# Multimeter1_2.net
KiCad netlist of a schematic drawn in EAGLE
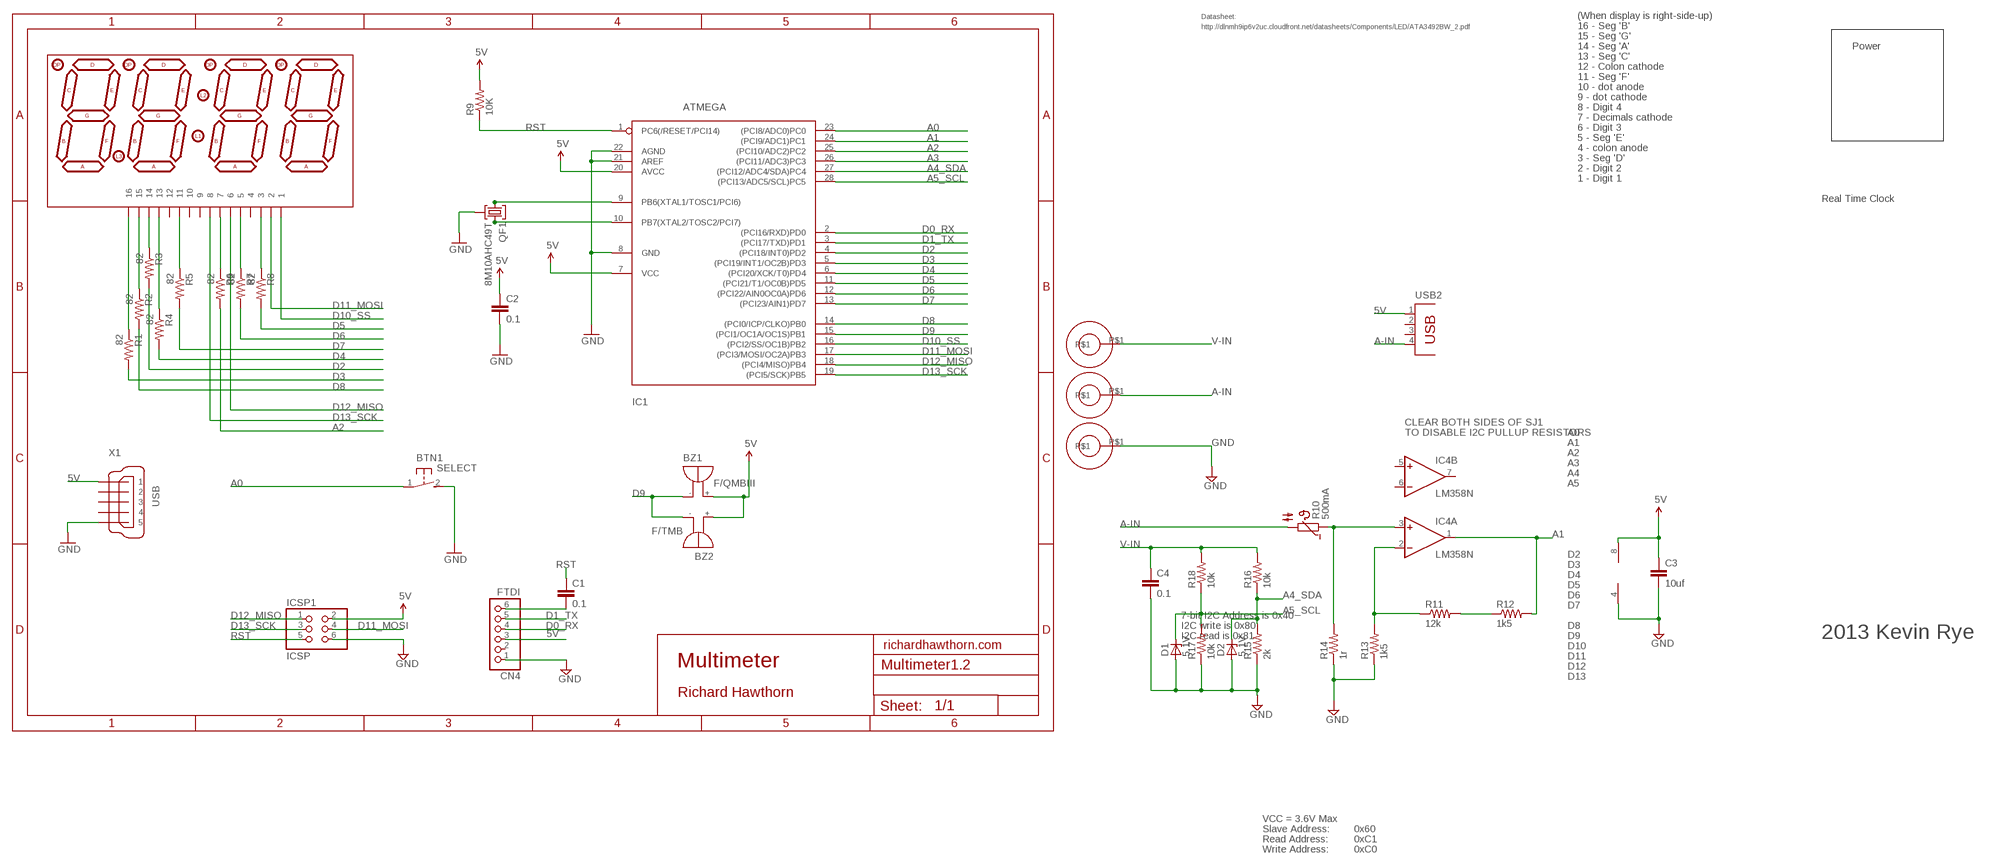
[diagram p0: schematic, sheet 1]

(export (version "E")
  (design (tool "Eeschema 10.0.6"))
  (components
    (comp (ref "BTN1")
      (value "SELECT")
      (footprint "eagle-import:DTS-3")
      (libsource (lib "eagle-import") (part "DTS-3"))
    )
    (comp (ref "BZ1")
      (value "F/QMBIII")
      (footprint "eagle-import:F_QMBIII")
      (libsource (lib "eagle-import") (part "F/QMBIII"))
    )
    (comp (ref "BZ2")
      (value "F/TMB")
      (footprint "eagle-import:F_TMB")
      (libsource (lib "eagle-import") (part "F/TMB"))
    )
    (comp (ref "C1")
      (value "0.1")
      (footprint "eagle-import:CAP-PTH-SMALL2")
      (libsource (lib "eagle-import") (part "CAPPTH2"))
    )
    (comp (ref "C2")
      (value "0.1")
      (footprint "eagle-import:CAP-PTH-SMALL2")
      (libsource (lib "eagle-import") (part "CAPPTH2"))
    )
    (comp (ref "C3")
      (value "10uf")
      (footprint "eagle-import:CAP-PTH-SMALL2")
      (libsource (lib "eagle-import") (part "CAPPTH2"))
    )
    (comp (ref "C4")
      (value "0.1")
      (footprint "eagle-import:CAP-PTH-SMALL2")
      (libsource (lib "eagle-import") (part "CAPPTH2"))
    )
    (comp (ref "CN4")
      (value "FTDI")
      (footprint "eagle-import:1X06")
      (libsource (lib "eagle-import") (part "PINHD-1X6"))
    )
    (comp (ref "D1")
      (value "5.1V")
      (footprint "eagle-import:DO34Z7")
      (libsource (lib "eagle-import") (part "BZX90"))
    )
    (comp (ref "D2")
      (value "5.1V")
      (footprint "eagle-import:DO34Z7")
      (libsource (lib "eagle-import") (part "BZX90"))
    )
    (comp (ref "IC1")
      (value "ATMEGA")
      (footprint "eagle-import:DIL28-3-ROUND")
      (libsource (lib "eagle-import") (part "ATMEGA168PROUND"))
    )
    (comp (ref "IC4")
      (value "LM358N")
      (footprint "eagle-import:DIL08")
      (libsource (lib "eagle-import") (part "LM358N"))
    )
    (comp (ref "ICSP1")
      (value "ICSP")
      (footprint "eagle-import:2X03")
      (libsource (lib "eagle-import") (part "PINHD-2X3"))
    )
    (comp (ref "LED1")
      (value "7SEG-4DIGIT")
      (footprint "eagle-import:SPARKFUN_7-SEGMENT-4DIGIT")
      (libsource (lib "eagle-import") (part "7SEG-4DIGIT"))
    )
    (comp (ref "QF1")
      (value "8M10AHC49T")
      (footprint "eagle-import:HC49U")
      (libsource (lib "eagle-import") (part "8M10AHC49T"))
    )
    (comp (ref "R1")
      (value "82")
      (footprint "eagle-import:0204_7")
      (libsource (lib "eagle-import") (part "R-US_0204/7"))
    )
    (comp (ref "R2")
      (value "82")
      (footprint "eagle-import:0204_7")
      (libsource (lib "eagle-import") (part "R-US_0204/7"))
    )
    (comp (ref "R3")
      (value "82")
      (footprint "eagle-import:0204_7")
      (libsource (lib "eagle-import") (part "R-US_0204/7"))
    )
    (comp (ref "R4")
      (value "82")
      (footprint "eagle-import:0204_7")
      (libsource (lib "eagle-import") (part "R-US_0204/7"))
    )
    (comp (ref "R5")
      (value "82")
      (footprint "eagle-import:0204_7")
      (libsource (lib "eagle-import") (part "R-US_0204/7"))
    )
    (comp (ref "R6")
      (value "82")
      (footprint "eagle-import:0204_7")
      (libsource (lib "eagle-import") (part "R-US_0204/7"))
    )
    (comp (ref "R7")
      (value "82")
      (footprint "eagle-import:0204_7")
      (libsource (lib "eagle-import") (part "R-US_0204/7"))
    )
    (comp (ref "R8")
      (value "82")
      (footprint "eagle-import:0204_7")
      (libsource (lib "eagle-import") (part "R-US_0204/7"))
    )
    (comp (ref "R9")
      (value "10K")
      (footprint "eagle-import:0204_7")
      (libsource (lib "eagle-import") (part "R-US_0204/7"))
    )
    (comp (ref "R10")
      (value "500mA")
      (footprint "eagle-import:B57164")
      (fields (field (name "MPN") "B57164K474K52"))
      (libsource (lib "eagle-import") (part "B57164"))
    )
    (comp (ref "R11")
      (value "12k")
      (footprint "eagle-import:0204_7")
      (libsource (lib "eagle-import") (part "R-US_0204/7"))
    )
    (comp (ref "R12")
      (value "1k5")
      (footprint "eagle-import:0204_7")
      (libsource (lib "eagle-import") (part "R-US_0204/7"))
    )
    (comp (ref "R13")
      (value "1k5")
      (footprint "eagle-import:0204_7")
      (libsource (lib "eagle-import") (part "R-US_0204/7"))
    )
    (comp (ref "R14")
      (value "1r")
      (footprint "eagle-import:0204_7")
      (libsource (lib "eagle-import") (part "R-US_0204/7"))
    )
    (comp (ref "R15")
      (value "2k")
      (footprint "eagle-import:0204_7")
      (libsource (lib "eagle-import") (part "R-US_0204/7"))
    )
    (comp (ref "R16")
      (value "10k")
      (footprint "eagle-import:0204_7")
      (libsource (lib "eagle-import") (part "R-US_0204/7"))
    )
    (comp (ref "R17")
      (value "10k")
      (footprint "eagle-import:0204_7")
      (libsource (lib "eagle-import") (part "R-US_0204/7"))
    )
    (comp (ref "R18")
      (value "10k")
      (footprint "eagle-import:0204_7")
      (libsource (lib "eagle-import") (part "R-US_0204/7"))
    )
    (comp (ref "U$1")
      (value "BANANA")
      (footprint "eagle-import:BANANA")
      (libsource (lib "eagle-import") (part "BANANA"))
    )
    (comp (ref "U$5")
      (value "BANANA")
      (footprint "eagle-import:BANANA")
      (libsource (lib "eagle-import") (part "BANANA"))
    )
    (comp (ref "U$6")
      (value "BANANA")
      (footprint "eagle-import:BANANA")
      (libsource (lib "eagle-import") (part "BANANA"))
    )
    (comp (ref "USB2")
      (value "PN87520")
      (footprint "eagle-import:PN87520")
      (libsource (lib "eagle-import") (part "PN87520"))
    )
    (comp (ref "X1")
      (value "USB")
      (footprint "eagle-import:32005-601")
      (libsource (lib "eagle-import") (part "MINI-USB_SHIELD5P2-32005-601"))
    )
  )
  (nets
    (net (code "1") (name "/A-IN") (class "Default")
      (node (ref "R10") (pin "2") (pinfunction "2_2") (pintype "passive"))
      (node (ref "U$5") (pin "P$1") (pinfunction "P$1_P$1") (pintype "bidirectional"))
      (node (ref "USB2") (pin "4") (pinfunction "4_4") (pintype "passive"))
    )
    (net (code "2") (name "/A0") (class "Default")
      (node (ref "BTN1") (pin "1") (pinfunction "1_1") (pintype "passive"))
      (node (ref "IC1") (pin "23") (pinfunction "(PCI8/ADC0)PC0_23") (pintype "bidirectional"))
    )
    (net (code "3") (name "/A1") (class "Default")
      (node (ref "IC1") (pin "24") (pinfunction "(PCI9/ADC1)PC1_24") (pintype "bidirectional"))
      (node (ref "IC4") (pin "1") (pinfunction "OUT_1") (pintype "output"))
      (node (ref "R12") (pin "2") (pinfunction "2_2") (pintype "passive"))
    )
    (net (code "4") (name "/A2") (class "Default")
      (node (ref "IC1") (pin "25") (pinfunction "(PCI10/ADC2)PC2_25") (pintype "bidirectional"))
      (node (ref "R6") (pin "2") (pinfunction "2_2") (pintype "passive"))
    )
    (net (code "5") (name "/A3") (class "Default")
      (node (ref "IC1") (pin "26") (pinfunction "(PCI11/ADC3)PC3_26") (pintype "bidirectional"))
    )
    (net (code "6") (name "/A4_SDA") (class "Default")
      (node (ref "D2") (pin "C") (pinfunction "C_C") (pintype "passive"))
      (node (ref "IC1") (pin "27") (pinfunction "(PCI12/ADC4/SDA)PC4_27") (pintype "bidirectional"))
      (node (ref "R15") (pin "2") (pinfunction "2_2") (pintype "passive"))
      (node (ref "R16") (pin "1") (pinfunction "1_1") (pintype "passive"))
    )
    (net (code "7") (name "/A5_SCL") (class "Default")
      (node (ref "D1") (pin "C") (pinfunction "C_C") (pintype "passive"))
      (node (ref "IC1") (pin "28") (pinfunction "(PCI13/ADC5/SCL)PC5_28") (pintype "bidirectional"))
      (node (ref "R17") (pin "2") (pinfunction "2_2") (pintype "passive"))
      (node (ref "R18") (pin "1") (pinfunction "1_1") (pintype "passive"))
    )
    (net (code "8") (name "/D0_RX") (class "Default")
      (node (ref "CN4") (pin "4") (pinfunction "4_4") (pintype "passive"))
      (node (ref "IC1") (pin "2") (pinfunction "(PCI16/RXD)PD0_2") (pintype "bidirectional"))
    )
    (net (code "9") (name "/D1_TX") (class "Default")
      (node (ref "CN4") (pin "5") (pinfunction "5_5") (pintype "passive"))
      (node (ref "IC1") (pin "3") (pinfunction "(PCI17/TXD)PD1_3") (pintype "bidirectional"))
    )
    (net (code "10") (name "/D2") (class "Default")
      (node (ref "IC1") (pin "4") (pinfunction "(PCI18/INT0)PD2_4") (pintype "bidirectional"))
      (node (ref "R3") (pin "2") (pinfunction "2_2") (pintype "passive"))
    )
    (net (code "11") (name "/D3") (class "Default")
      (node (ref "IC1") (pin "5") (pinfunction "(PCI19/INT1/OC2B)PD3_5") (pintype "bidirectional"))
      (node (ref "R1") (pin "2") (pinfunction "2_2") (pintype "passive"))
    )
    (net (code "12") (name "/D4") (class "Default")
      (node (ref "IC1") (pin "6") (pinfunction "(PCI20/XCK/T0)PD4_6") (pintype "bidirectional"))
      (node (ref "R4") (pin "2") (pinfunction "2_2") (pintype "passive"))
    )
    (net (code "13") (name "/D5") (class "Default")
      (node (ref "IC1") (pin "11") (pinfunction "(PCI21/T1/OC0B)PD5_11") (pintype "bidirectional"))
      (node (ref "R8") (pin "2") (pinfunction "2_2") (pintype "passive"))
    )
    (net (code "14") (name "/D6") (class "Default")
      (node (ref "IC1") (pin "12") (pinfunction "(PCI22/AIN0OC0A)PD6_12") (pintype "bidirectional"))
      (node (ref "R7") (pin "2") (pinfunction "2_2") (pintype "passive"))
    )
    (net (code "15") (name "/D7") (class "Default")
      (node (ref "IC1") (pin "13") (pinfunction "(PCI23/AIN1)PD7_13") (pintype "bidirectional"))
      (node (ref "R5") (pin "2") (pinfunction "2_2") (pintype "passive"))
    )
    (net (code "16") (name "/D8") (class "Default")
      (node (ref "IC1") (pin "14") (pinfunction "(PCI0/ICP/CLKO)PB0_14") (pintype "bidirectional"))
      (node (ref "R2") (pin "2") (pinfunction "2_2") (pintype "passive"))
    )
    (net (code "17") (name "/D9") (class "Default")
      (node (ref "BZ1") (pin "-") (pinfunction "+_-") (pintype "passive"))
      (node (ref "BZ2") (pin "-") (pinfunction "-_-") (pintype "passive"))
      (node (ref "IC1") (pin "15") (pinfunction "(PCI1/OC1A/OC1S)PB1_15") (pintype "bidirectional"))
    )
    (net (code "18") (name "/D10_SS") (class "Default")
      (node (ref "IC1") (pin "16") (pinfunction "(PCI2/SS/OC1B)PB2_16") (pintype "bidirectional"))
      (node (ref "LED1") (pin "1") (pinfunction "1_1") (pintype "bidirectional"))
    )
    (net (code "19") (name "/D11_MOSI") (class "Default")
      (node (ref "IC1") (pin "17") (pinfunction "(PCI3/MOSI/OC2A)PB3_17") (pintype "bidirectional"))
      (node (ref "ICSP1") (pin "4") (pinfunction "4_4") (pintype "passive"))
      (node (ref "LED1") (pin "2") (pinfunction "2_2") (pintype "bidirectional"))
    )
    (net (code "20") (name "/D12_MISO") (class "Default")
      (node (ref "IC1") (pin "18") (pinfunction "(PCI4/MISO)PB4_18") (pintype "bidirectional"))
      (node (ref "ICSP1") (pin "1") (pinfunction "1_1") (pintype "passive"))
      (node (ref "LED1") (pin "6") (pinfunction "6_6") (pintype "bidirectional"))
    )
    (net (code "21") (name "/D13_SCK") (class "Default")
      (node (ref "IC1") (pin "19") (pinfunction "(PCI5/SCK)PB5_19") (pintype "bidirectional"))
      (node (ref "ICSP1") (pin "3") (pinfunction "3_3") (pintype "passive"))
      (node (ref "LED1") (pin "8") (pinfunction "8_8") (pintype "bidirectional"))
    )
    (net (code "22") (name "/RST") (class "Default")
      (node (ref "C1") (pin "1") (pinfunction "1_1") (pintype "passive"))
      (node (ref "IC1") (pin "1") (pinfunction "PC6(/RESET/PCI14)_1") (pintype "bidirectional"))
      (node (ref "ICSP1") (pin "5") (pinfunction "5_5") (pintype "passive"))
      (node (ref "R9") (pin "1") (pinfunction "1_1") (pintype "passive"))
    )
    (net (code "23") (name "/V-IN") (class "Default")
      (node (ref "C4") (pin "1") (pinfunction "1_1") (pintype "passive"))
      (node (ref "R16") (pin "2") (pinfunction "2_2") (pintype "passive"))
      (node (ref "R18") (pin "2") (pinfunction "2_2") (pintype "passive"))
      (node (ref "U$1") (pin "P$1") (pinfunction "P$1_P$1") (pintype "bidirectional"))
    )
    (net (code "24") (name "5V") (class "Default")
      (node (ref "BZ1") (pin "+") (pinfunction "-_+") (pintype "passive"))
      (node (ref "BZ2") (pin "+") (pinfunction "+_+") (pintype "passive"))
      (node (ref "C2") (pin "1") (pinfunction "1_1") (pintype "passive"))
      (node (ref "C3") (pin "1") (pinfunction "1_1") (pintype "passive"))
      (node (ref "CN4") (pin "3") (pinfunction "3_3") (pintype "passive"))
      (node (ref "IC1") (pin "20") (pinfunction "AVCC_20") (pintype "bidirectional"))
      (node (ref "IC1") (pin "7") (pinfunction "VCC_7") (pintype "bidirectional"))
      (node (ref "IC4") (pin "8") (pinfunction "V+_8") (pintype "power_in"))
      (node (ref "ICSP1") (pin "2") (pinfunction "2_2") (pintype "passive"))
      (node (ref "R9") (pin "2") (pinfunction "2_2") (pintype "passive"))
      (node (ref "USB2") (pin "1") (pinfunction "1_1") (pintype "passive"))
      (node (ref "X1") (pin "1") (pinfunction "1_1") (pintype "passive"))
    )
    (net (code "25") (name "GND") (class "Default")
      (node (ref "BTN1") (pin "2") (pinfunction "2_2") (pintype "passive"))
      (node (ref "C2") (pin "2") (pinfunction "2_2") (pintype "passive"))
      (node (ref "C3") (pin "2") (pinfunction "2_2") (pintype "passive"))
      (node (ref "C4") (pin "2") (pinfunction "2_2") (pintype "passive"))
      (node (ref "CN4") (pin "1") (pinfunction "1_1") (pintype "passive"))
      (node (ref "D1") (pin "A") (pinfunction "A_A") (pintype "passive"))
      (node (ref "D2") (pin "A") (pinfunction "A_A") (pintype "passive"))
      (node (ref "IC1") (pin "21") (pinfunction "AREF_21") (pintype "bidirectional"))
      (node (ref "IC1") (pin "22") (pinfunction "AGND_22") (pintype "bidirectional"))
      (node (ref "IC1") (pin "8") (pinfunction "GND_8") (pintype "bidirectional"))
      (node (ref "IC4") (pin "4") (pinfunction "V-_4") (pintype "power_in"))
      (node (ref "ICSP1") (pin "6") (pinfunction "6_6") (pintype "passive"))
      (node (ref "QF1") (pin "2") (pinfunction "2_2") (pintype "passive"))
      (node (ref "R13") (pin "1") (pinfunction "1_1") (pintype "passive"))
      (node (ref "R14") (pin "1") (pinfunction "1_1") (pintype "passive"))
      (node (ref "R15") (pin "1") (pinfunction "1_1") (pintype "passive"))
      (node (ref "R17") (pin "1") (pinfunction "1_1") (pintype "passive"))
      (node (ref "U$6") (pin "P$1") (pinfunction "P$1_P$1") (pintype "bidirectional"))
      (node (ref "X1") (pin "5") (pinfunction "5_5") (pintype "passive"))
    )
    (net (code "26") (name "Net-(C1-Pad2)") (class "Default")
      (node (ref "C1") (pin "2") (pinfunction "2_2") (pintype "passive"))
      (node (ref "CN4") (pin "6") (pinfunction "6_6") (pintype "passive"))
    )
    (net (code "27") (name "Net-(IC1-PB6(XTAL1{slash}TOSC1{slash}PCI6))") (class "Default")
      (node (ref "IC1") (pin "9") (pinfunction "PB6(XTAL1/TOSC1/PCI6)_9") (pintype "bidirectional"))
      (node (ref "QF1") (pin "1") (pinfunction "1_1") (pintype "passive"))
    )
    (net (code "28") (name "Net-(IC1-PB7(XTAL2{slash}TOSC2{slash}PCI7))") (class "Default")
      (node (ref "IC1") (pin "10") (pinfunction "PB7(XTAL2/TOSC2/PCI7)_10") (pintype "bidirectional"))
      (node (ref "QF1") (pin "3") (pinfunction "3_3") (pintype "passive"))
    )
    (net (code "29") (name "Net-(IC4A-+IN)") (class "Default")
      (node (ref "IC4") (pin "3") (pinfunction "+IN_3") (pintype "input"))
      (node (ref "R10") (pin "1") (pinfunction "1_1") (pintype "passive"))
      (node (ref "R14") (pin "2") (pinfunction "2_2") (pintype "passive"))
    )
    (net (code "30") (name "Net-(IC4A--IN)") (class "Default")
      (node (ref "IC4") (pin "2") (pinfunction "-IN_2") (pintype "input"))
      (node (ref "R11") (pin "1") (pinfunction "1_1") (pintype "passive"))
      (node (ref "R13") (pin "2") (pinfunction "2_2") (pintype "passive"))
    )
    (net (code "31") (name "Net-(LED1-Pad3)") (class "Default")
      (node (ref "LED1") (pin "3") (pinfunction "3_3") (pintype "bidirectional"))
      (node (ref "R8") (pin "1") (pinfunction "1_1") (pintype "passive"))
    )
    (net (code "32") (name "Net-(LED1-Pad5)") (class "Default")
      (node (ref "LED1") (pin "5") (pinfunction "5_5") (pintype "bidirectional"))
      (node (ref "R7") (pin "1") (pinfunction "1_1") (pintype "passive"))
    )
    (net (code "33") (name "Net-(LED1-Pad7)") (class "Default")
      (node (ref "LED1") (pin "7") (pinfunction "7_7") (pintype "bidirectional"))
      (node (ref "R6") (pin "1") (pinfunction "1_1") (pintype "passive"))
    )
    (net (code "34") (name "Net-(LED1-Pad11)") (class "Default")
      (node (ref "LED1") (pin "11") (pinfunction "11_11") (pintype "bidirectional"))
      (node (ref "R5") (pin "1") (pinfunction "1_1") (pintype "passive"))
    )
    (net (code "35") (name "Net-(LED1-Pad13)") (class "Default")
      (node (ref "LED1") (pin "13") (pinfunction "13_13") (pintype "bidirectional"))
      (node (ref "R4") (pin "1") (pinfunction "1_1") (pintype "passive"))
    )
    (net (code "36") (name "Net-(LED1-Pad14)") (class "Default")
      (node (ref "LED1") (pin "14") (pinfunction "14_14") (pintype "bidirectional"))
      (node (ref "R3") (pin "1") (pinfunction "1_1") (pintype "passive"))
    )
    (net (code "37") (name "Net-(LED1-Pad15)") (class "Default")
      (node (ref "LED1") (pin "15") (pinfunction "15_15") (pintype "bidirectional"))
      (node (ref "R2") (pin "1") (pinfunction "1_1") (pintype "passive"))
    )
    (net (code "38") (name "Net-(LED1-Pad16)") (class "Default")
      (node (ref "LED1") (pin "16") (pinfunction "16_16") (pintype "bidirectional"))
      (node (ref "R1") (pin "1") (pinfunction "1_1") (pintype "passive"))
    )
    (net (code "39") (name "Net-(R11-Pad2)") (class "Default")
      (node (ref "R11") (pin "2") (pinfunction "2_2") (pintype "passive"))
      (node (ref "R12") (pin "1") (pinfunction "1_1") (pintype "passive"))
    )
    (net (code "40") (name "unconnected-(CN4-Pad2)") (class "Default")
      (node (ref "CN4") (pin "2") (pinfunction "2_2") (pintype "passive"))
    )
    (net (code "41") (name "unconnected-(IC4B-+IN-Pad5)") (class "Default")
      (node (ref "IC4") (pin "5") (pinfunction "+IN_5") (pintype "input"))
    )
    (net (code "42") (name "unconnected-(IC4B--IN-Pad6)") (class "Default")
      (node (ref "IC4") (pin "6") (pinfunction "-IN_6") (pintype "input"))
    )
    (net (code "43") (name "unconnected-(IC4B-OUT-Pad7)") (class "Default")
      (node (ref "IC4") (pin "7") (pinfunction "OUT_7") (pintype "output"))
    )
    (net (code "44") (name "unconnected-(LED1-Pad4)") (class "Default")
      (node (ref "LED1") (pin "4") (pinfunction "4_4") (pintype "bidirectional"))
    )
    (net (code "45") (name "unconnected-(LED1-Pad9)") (class "Default")
      (node (ref "LED1") (pin "9") (pinfunction "9_9") (pintype "bidirectional"))
    )
    (net (code "46") (name "unconnected-(LED1-Pad10)") (class "Default")
      (node (ref "LED1") (pin "10") (pinfunction "10_10") (pintype "bidirectional"))
    )
    (net (code "47") (name "unconnected-(LED1-Pad12)") (class "Default")
      (node (ref "LED1") (pin "12") (pinfunction "12_12") (pintype "bidirectional"))
    )
    (net (code "48") (name "unconnected-(USB2-Pad2)") (class "Default")
      (node (ref "USB2") (pin "2") (pinfunction "2_2") (pintype "passive"))
    )
    (net (code "49") (name "unconnected-(USB2-Pad3)") (class "Default")
      (node (ref "USB2") (pin "3") (pinfunction "3_3") (pintype "passive"))
    )
    (net (code "50") (name "unconnected-(X1-Pad2)") (class "Default")
      (node (ref "X1") (pin "2") (pinfunction "2_2") (pintype "passive"))
    )
    (net (code "51") (name "unconnected-(X1-Pad3)") (class "Default")
      (node (ref "X1") (pin "3") (pinfunction "3_3") (pintype "passive"))
    )
    (net (code "52") (name "unconnected-(X1-Pad4)") (class "Default")
      (node (ref "X1") (pin "4") (pinfunction "4_4") (pintype "passive"))
    )
  )
)
